# IR_LED_Version2.net
KiCad netlist of a schematic drawn in EAGLE
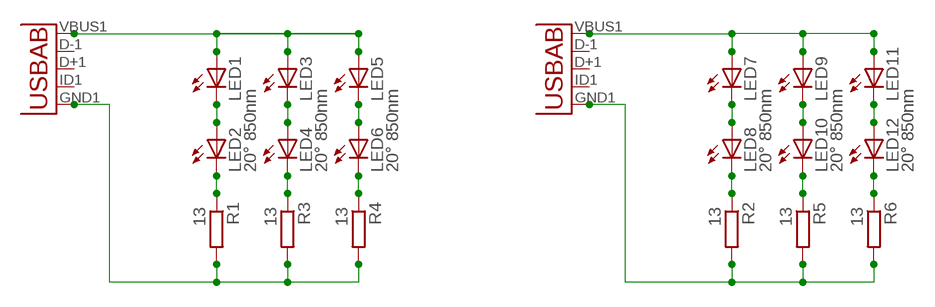
[diagram p0: schematic, sheet 1]

(export (version "E")
  (design (tool "Eeschema 10.0.6"))
  (components
    (comp (ref "LED1")
      (value "LED5MM")
      (footprint "eagle-import:LED5MM")
      (libsource (lib "eagle-import") (part "LED5MM"))
    )
    (comp (ref "LED2")
      (value "20° 850nm")
      (footprint "eagle-import:LED5MM")
      (libsource (lib "eagle-import") (part "LED5MM"))
    )
    (comp (ref "LED3")
      (value "LED5MM")
      (footprint "eagle-import:LED5MM")
      (libsource (lib "eagle-import") (part "LED5MM"))
    )
    (comp (ref "LED4")
      (value "20° 850nm")
      (footprint "eagle-import:LED5MM")
      (libsource (lib "eagle-import") (part "LED5MM"))
    )
    (comp (ref "LED5")
      (value "LED5MM")
      (footprint "eagle-import:LED5MM")
      (libsource (lib "eagle-import") (part "LED5MM"))
    )
    (comp (ref "LED6")
      (value "20° 850nm")
      (footprint "eagle-import:LED5MM")
      (libsource (lib "eagle-import") (part "LED5MM"))
    )
    (comp (ref "LED7")
      (value "LED5MM")
      (footprint "eagle-import:LED5MM")
      (libsource (lib "eagle-import") (part "LED5MM"))
    )
    (comp (ref "LED8")
      (value "20° 850nm")
      (footprint "eagle-import:LED5MM")
      (libsource (lib "eagle-import") (part "LED5MM"))
    )
    (comp (ref "LED9")
      (value "LED5MM")
      (footprint "eagle-import:LED5MM")
      (libsource (lib "eagle-import") (part "LED5MM"))
    )
    (comp (ref "LED10")
      (value "20° 850nm")
      (footprint "eagle-import:LED5MM")
      (libsource (lib "eagle-import") (part "LED5MM"))
    )
    (comp (ref "LED11")
      (value "LED5MM")
      (footprint "eagle-import:LED5MM")
      (libsource (lib "eagle-import") (part "LED5MM"))
    )
    (comp (ref "LED12")
      (value "20° 850nm")
      (footprint "eagle-import:LED5MM")
      (libsource (lib "eagle-import") (part "LED5MM"))
    )
    (comp (ref "R1")
      (value "13")
      (footprint "eagle-import:0204_7")
      (libsource (lib "eagle-import") (part "R-EU_0204/7"))
    )
    (comp (ref "R2")
      (value "13")
      (footprint "eagle-import:0204_7")
      (libsource (lib "eagle-import") (part "R-EU_0204/7"))
    )
    (comp (ref "R3")
      (value "13")
      (footprint "eagle-import:0204_7")
      (libsource (lib "eagle-import") (part "R-EU_0204/7"))
    )
    (comp (ref "R4")
      (value "13")
      (footprint "eagle-import:0204_7")
      (libsource (lib "eagle-import") (part "R-EU_0204/7"))
    )
    (comp (ref "R5")
      (value "13")
      (footprint "eagle-import:0204_7")
      (libsource (lib "eagle-import") (part "R-EU_0204/7"))
    )
    (comp (ref "R6")
      (value "13")
      (footprint "eagle-import:0204_7")
      (libsource (lib "eagle-import") (part "R-EU_0204/7"))
    )
    (comp (ref "U1")
      (value "USB\"\"")
      (footprint "eagle-import:USB-MICRO-SMD")
      (libsource (lib "eagle-import") (part "USB{dblquote}{dblquote}"))
    )
    (comp (ref "U2")
      (value "USB\"\"")
      (footprint "eagle-import:USB-MICRO-SMD")
      (libsource (lib "eagle-import") (part "USB{dblquote}{dblquote}"))
    )
  )
  (nets
    (net (code "1") (name "Net-(LED1-C)") (class "Default")
      (node (ref "LED1") (pin "K") (pinfunction "C_K") (pintype "passive"))
      (node (ref "LED2") (pin "A") (pinfunction "A_A") (pintype "passive"))
    )
    (net (code "2") (name "Net-(LED2-C)") (class "Default")
      (node (ref "LED2") (pin "K") (pinfunction "C_K") (pintype "passive"))
      (node (ref "R1") (pin "1") (pinfunction "1_1") (pintype "passive"))
    )
    (net (code "3") (name "Net-(LED3-C)") (class "Default")
      (node (ref "LED3") (pin "K") (pinfunction "C_K") (pintype "passive"))
      (node (ref "LED4") (pin "A") (pinfunction "A_A") (pintype "passive"))
    )
    (net (code "4") (name "Net-(LED4-C)") (class "Default")
      (node (ref "LED4") (pin "K") (pinfunction "C_K") (pintype "passive"))
      (node (ref "R3") (pin "1") (pinfunction "1_1") (pintype "passive"))
    )
    (net (code "5") (name "Net-(LED5-C)") (class "Default")
      (node (ref "LED5") (pin "K") (pinfunction "C_K") (pintype "passive"))
      (node (ref "LED6") (pin "A") (pinfunction "A_A") (pintype "passive"))
    )
    (net (code "6") (name "Net-(LED6-C)") (class "Default")
      (node (ref "LED6") (pin "K") (pinfunction "C_K") (pintype "passive"))
      (node (ref "R4") (pin "1") (pinfunction "1_1") (pintype "passive"))
    )
    (net (code "7") (name "Net-(LED7-C)") (class "Default")
      (node (ref "LED7") (pin "K") (pinfunction "C_K") (pintype "passive"))
      (node (ref "LED8") (pin "A") (pinfunction "A_A") (pintype "passive"))
    )
    (net (code "8") (name "Net-(LED8-C)") (class "Default")
      (node (ref "LED8") (pin "K") (pinfunction "C_K") (pintype "passive"))
      (node (ref "R2") (pin "1") (pinfunction "1_1") (pintype "passive"))
    )
    (net (code "9") (name "Net-(LED9-C)") (class "Default")
      (node (ref "LED10") (pin "A") (pinfunction "A_A") (pintype "passive"))
      (node (ref "LED9") (pin "K") (pinfunction "C_K") (pintype "passive"))
    )
    (net (code "10") (name "Net-(LED10-C)") (class "Default")
      (node (ref "LED10") (pin "K") (pinfunction "C_K") (pintype "passive"))
      (node (ref "R5") (pin "1") (pinfunction "1_1") (pintype "passive"))
    )
    (net (code "11") (name "Net-(LED11-C)") (class "Default")
      (node (ref "LED11") (pin "K") (pinfunction "C_K") (pintype "passive"))
      (node (ref "LED12") (pin "A") (pinfunction "A_A") (pintype "passive"))
    )
    (net (code "12") (name "Net-(LED12-C)") (class "Default")
      (node (ref "LED12") (pin "K") (pinfunction "C_K") (pintype "passive"))
      (node (ref "R6") (pin "1") (pinfunction "1_1") (pintype "passive"))
    )
    (net (code "13") (name "Net-(U1-GND)") (class "Default")
      (node (ref "R1") (pin "2") (pinfunction "2_2") (pintype "passive"))
      (node (ref "R3") (pin "2") (pinfunction "2_2") (pintype "passive"))
      (node (ref "R4") (pin "2") (pinfunction "2_2") (pintype "passive"))
      (node (ref "U1") (pin "GND1") (pinfunction "GND_GND1") (pintype "bidirectional"))
    )
    (net (code "14") (name "Net-(U1-VBUS)") (class "Default")
      (node (ref "LED1") (pin "A") (pinfunction "A_A") (pintype "passive"))
      (node (ref "LED3") (pin "A") (pinfunction "A_A") (pintype "passive"))
      (node (ref "LED5") (pin "A") (pinfunction "A_A") (pintype "passive"))
      (node (ref "U1") (pin "VBUS1") (pinfunction "VBUS_VBUS1") (pintype "bidirectional"))
    )
    (net (code "15") (name "Net-(U2-GND)") (class "Default")
      (node (ref "R2") (pin "2") (pinfunction "2_2") (pintype "passive"))
      (node (ref "R5") (pin "2") (pinfunction "2_2") (pintype "passive"))
      (node (ref "R6") (pin "2") (pinfunction "2_2") (pintype "passive"))
      (node (ref "U2") (pin "GND1") (pinfunction "GND_GND1") (pintype "bidirectional"))
    )
    (net (code "16") (name "Net-(U2-VBUS)") (class "Default")
      (node (ref "LED11") (pin "A") (pinfunction "A_A") (pintype "passive"))
      (node (ref "LED7") (pin "A") (pinfunction "A_A") (pintype "passive"))
      (node (ref "LED9") (pin "A") (pinfunction "A_A") (pintype "passive"))
      (node (ref "U2") (pin "VBUS1") (pinfunction "VBUS_VBUS1") (pintype "bidirectional"))
    )
    (net (code "17") (name "unconnected-(U1-D+-PadD+1)") (class "Default")
      (node (ref "U1") (pin "D+1") (pinfunction "D+_D+1") (pintype "bidirectional"))
    )
    (net (code "18") (name "unconnected-(U1-D--PadD-1)") (class "Default")
      (node (ref "U1") (pin "D-1") (pinfunction "D-_D-1") (pintype "bidirectional"))
    )
    (net (code "19") (name "unconnected-(U1-USBID-PadID1)") (class "Default")
      (node (ref "U1") (pin "ID1") (pinfunction "USBID_ID1") (pintype "bidirectional"))
    )
    (net (code "20") (name "unconnected-(U2-D+-PadD+1)") (class "Default")
      (node (ref "U2") (pin "D+1") (pinfunction "D+_D+1") (pintype "bidirectional"))
    )
    (net (code "21") (name "unconnected-(U2-D--PadD-1)") (class "Default")
      (node (ref "U2") (pin "D-1") (pinfunction "D-_D-1") (pintype "bidirectional"))
    )
    (net (code "22") (name "unconnected-(U2-USBID-PadID1)") (class "Default")
      (node (ref "U2") (pin "ID1") (pinfunction "USBID_ID1") (pintype "bidirectional"))
    )
  )
)
